# RFID_Brd_01.net
KiCad netlist of a schematic drawn in EAGLE
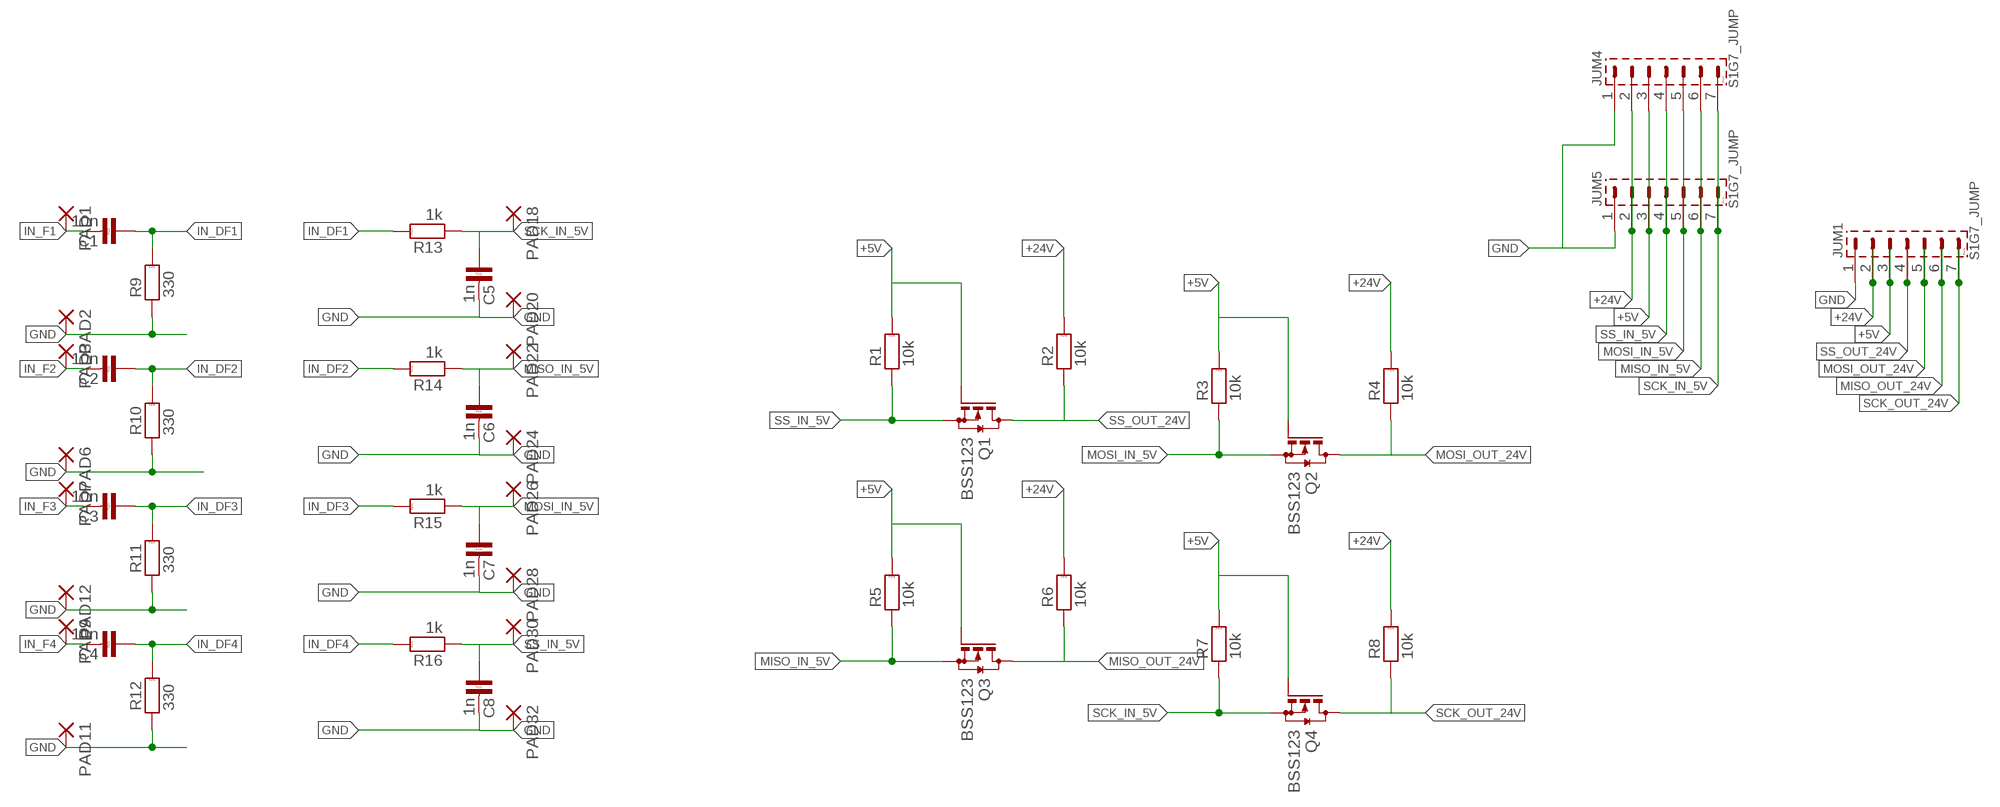
[diagram p0: schematic, sheet 1]

(export (version "E")
  (design (tool "Eeschema 10.0.6"))
  (components
    (comp (ref "C1")
      (value "10n")
      (footprint "eagle-import:1206")
      (libsource (lib "eagle-import") (part "C-KER_1206"))
    )
    (comp (ref "C2")
      (value "10n")
      (footprint "eagle-import:1206")
      (libsource (lib "eagle-import") (part "C-KER_1206"))
    )
    (comp (ref "C3")
      (value "10n")
      (footprint "eagle-import:1206")
      (libsource (lib "eagle-import") (part "C-KER_1206"))
    )
    (comp (ref "C4")
      (value "10n")
      (footprint "eagle-import:1206")
      (libsource (lib "eagle-import") (part "C-KER_1206"))
    )
    (comp (ref "C5")
      (value "1n")
      (footprint "eagle-import:1206")
      (libsource (lib "eagle-import") (part "C-KER_1206"))
    )
    (comp (ref "C6")
      (value "1n")
      (footprint "eagle-import:1206")
      (libsource (lib "eagle-import") (part "C-KER_1206"))
    )
    (comp (ref "C7")
      (value "1n")
      (footprint "eagle-import:1206")
      (libsource (lib "eagle-import") (part "C-KER_1206"))
    )
    (comp (ref "C8")
      (value "1n")
      (footprint "eagle-import:1206")
      (libsource (lib "eagle-import") (part "C-KER_1206"))
    )
    (comp (ref "JUM1")
      (value "S1G7_JUMP")
      (footprint "eagle-import:S1G7_JUM")
      (libsource (lib "eagle-import") (part "S1G7_JUMP"))
    )
    (comp (ref "JUM4")
      (value "S1G7_JUMP")
      (footprint "eagle-import:S1G7_JUM")
      (libsource (lib "eagle-import") (part "S1G7_JUMP"))
    )
    (comp (ref "JUM5")
      (value "S1G7_JUMP")
      (footprint "eagle-import:S1G7_JUM")
      (libsource (lib "eagle-import") (part "S1G7_JUMP"))
    )
    (comp (ref "PAD1")
      (value "SMD2")
      (footprint "eagle-import:SMD1,27-2,54")
      (libsource (lib "eagle-import") (part "SMD2"))
    )
    (comp (ref "PAD2")
      (value "SMD2")
      (footprint "eagle-import:SMD1,27-2,54")
      (libsource (lib "eagle-import") (part "SMD2"))
    )
    (comp (ref "PAD3")
      (value "SMD2")
      (footprint "eagle-import:SMD1,27-2,54")
      (libsource (lib "eagle-import") (part "SMD2"))
    )
    (comp (ref "PAD6")
      (value "SMD2")
      (footprint "eagle-import:SMD1,27-2,54")
      (libsource (lib "eagle-import") (part "SMD2"))
    )
    (comp (ref "PAD7")
      (value "SMD2")
      (footprint "eagle-import:SMD1,27-2,54")
      (libsource (lib "eagle-import") (part "SMD2"))
    )
    (comp (ref "PAD9")
      (value "SMD2")
      (footprint "eagle-import:SMD1,27-2,54")
      (libsource (lib "eagle-import") (part "SMD2"))
    )
    (comp (ref "PAD11")
      (value "SMD2")
      (footprint "eagle-import:SMD1,27-2,54")
      (libsource (lib "eagle-import") (part "SMD2"))
    )
    (comp (ref "PAD12")
      (value "SMD2")
      (footprint "eagle-import:SMD1,27-2,54")
      (libsource (lib "eagle-import") (part "SMD2"))
    )
    (comp (ref "PAD18")
      (value "SMD2")
      (footprint "eagle-import:SMD1,27-2,54")
      (libsource (lib "eagle-import") (part "SMD2"))
    )
    (comp (ref "PAD20")
      (value "SMD2")
      (footprint "eagle-import:SMD1,27-2,54")
      (libsource (lib "eagle-import") (part "SMD2"))
    )
    (comp (ref "PAD22")
      (value "SMD2")
      (footprint "eagle-import:SMD1,27-2,54")
      (libsource (lib "eagle-import") (part "SMD2"))
    )
    (comp (ref "PAD24")
      (value "SMD2")
      (footprint "eagle-import:SMD1,27-2,54")
      (libsource (lib "eagle-import") (part "SMD2"))
    )
    (comp (ref "PAD26")
      (value "SMD2")
      (footprint "eagle-import:SMD1,27-2,54")
      (libsource (lib "eagle-import") (part "SMD2"))
    )
    (comp (ref "PAD28")
      (value "SMD2")
      (footprint "eagle-import:SMD1,27-2,54")
      (libsource (lib "eagle-import") (part "SMD2"))
    )
    (comp (ref "PAD30")
      (value "SMD2")
      (footprint "eagle-import:SMD1,27-2,54")
      (libsource (lib "eagle-import") (part "SMD2"))
    )
    (comp (ref "PAD32")
      (value "SMD2")
      (footprint "eagle-import:SMD1,27-2,54")
      (libsource (lib "eagle-import") (part "SMD2"))
    )
    (comp (ref "Q1")
      (value "BSS123")
      (footprint "eagle-import:SOT23")
      (libsource (lib "eagle-import") (part "BSS123"))
    )
    (comp (ref "Q2")
      (value "BSS123")
      (footprint "eagle-import:SOT23")
      (libsource (lib "eagle-import") (part "BSS123"))
    )
    (comp (ref "Q3")
      (value "BSS123")
      (footprint "eagle-import:SOT23")
      (libsource (lib "eagle-import") (part "BSS123"))
    )
    (comp (ref "Q4")
      (value "BSS123")
      (footprint "eagle-import:SOT23")
      (libsource (lib "eagle-import") (part "BSS123"))
    )
    (comp (ref "R1")
      (value "10k")
      (footprint "eagle-import:1206")
      (libsource (lib "eagle-import") (part "R_1206"))
    )
    (comp (ref "R2")
      (value "10k")
      (footprint "eagle-import:1206")
      (libsource (lib "eagle-import") (part "R_1206"))
    )
    (comp (ref "R3")
      (value "10k")
      (footprint "eagle-import:1206")
      (libsource (lib "eagle-import") (part "R_1206"))
    )
    (comp (ref "R4")
      (value "10k")
      (footprint "eagle-import:1206")
      (libsource (lib "eagle-import") (part "R_1206"))
    )
    (comp (ref "R5")
      (value "10k")
      (footprint "eagle-import:1206")
      (libsource (lib "eagle-import") (part "R_1206"))
    )
    (comp (ref "R6")
      (value "10k")
      (footprint "eagle-import:1206")
      (libsource (lib "eagle-import") (part "R_1206"))
    )
    (comp (ref "R7")
      (value "10k")
      (footprint "eagle-import:1206")
      (libsource (lib "eagle-import") (part "R_1206"))
    )
    (comp (ref "R8")
      (value "10k")
      (footprint "eagle-import:1206")
      (libsource (lib "eagle-import") (part "R_1206"))
    )
    (comp (ref "R9")
      (value "330")
      (footprint "eagle-import:1206")
      (libsource (lib "eagle-import") (part "R_1206"))
    )
    (comp (ref "R10")
      (value "330")
      (footprint "eagle-import:1206")
      (libsource (lib "eagle-import") (part "R_1206"))
    )
    (comp (ref "R11")
      (value "330")
      (footprint "eagle-import:1206")
      (libsource (lib "eagle-import") (part "R_1206"))
    )
    (comp (ref "R12")
      (value "330")
      (footprint "eagle-import:1206")
      (libsource (lib "eagle-import") (part "R_1206"))
    )
    (comp (ref "R13")
      (value "1k")
      (footprint "eagle-import:1206")
      (libsource (lib "eagle-import") (part "R_1206"))
    )
    (comp (ref "R14")
      (value "1k")
      (footprint "eagle-import:1206")
      (libsource (lib "eagle-import") (part "R_1206"))
    )
    (comp (ref "R15")
      (value "1k")
      (footprint "eagle-import:1206")
      (libsource (lib "eagle-import") (part "R_1206"))
    )
    (comp (ref "R16")
      (value "1k")
      (footprint "eagle-import:1206")
      (libsource (lib "eagle-import") (part "R_1206"))
    )
  )
  (nets
    (net (code "1") (name "+5V") (class "Default")
      (node (ref "JUM1") (pin "3") (pinfunction "3_3") (pintype "passive"))
      (node (ref "JUM4") (pin "3") (pinfunction "3_3") (pintype "passive"))
      (node (ref "JUM5") (pin "3") (pinfunction "3_3") (pintype "passive"))
      (node (ref "Q1") (pin "1") (pinfunction "G_1") (pintype "passive"))
      (node (ref "Q2") (pin "1") (pinfunction "G_1") (pintype "passive"))
      (node (ref "Q3") (pin "1") (pinfunction "G_1") (pintype "passive"))
      (node (ref "Q4") (pin "1") (pinfunction "G_1") (pintype "passive"))
      (node (ref "R1") (pin "2") (pinfunction "2_2") (pintype "passive"))
      (node (ref "R3") (pin "2") (pinfunction "2_2") (pintype "passive"))
      (node (ref "R5") (pin "2") (pinfunction "2_2") (pintype "passive"))
      (node (ref "R7") (pin "2") (pinfunction "2_2") (pintype "passive"))
    )
    (net (code "2") (name "+24V") (class "Default")
      (node (ref "JUM1") (pin "2") (pinfunction "2_2") (pintype "passive"))
      (node (ref "JUM4") (pin "2") (pinfunction "2_2") (pintype "passive"))
      (node (ref "JUM5") (pin "2") (pinfunction "2_2") (pintype "passive"))
      (node (ref "R2") (pin "2") (pinfunction "2_2") (pintype "passive"))
      (node (ref "R4") (pin "2") (pinfunction "2_2") (pintype "passive"))
      (node (ref "R6") (pin "2") (pinfunction "2_2") (pintype "passive"))
      (node (ref "R8") (pin "2") (pinfunction "2_2") (pintype "passive"))
    )
    (net (code "3") (name "GND") (class "Default")
      (node (ref "C5") (pin "2") (pinfunction "2_2") (pintype "passive"))
      (node (ref "C6") (pin "2") (pinfunction "2_2") (pintype "passive"))
      (node (ref "C7") (pin "2") (pinfunction "2_2") (pintype "passive"))
      (node (ref "C8") (pin "2") (pinfunction "2_2") (pintype "passive"))
      (node (ref "JUM1") (pin "1") (pinfunction "1_1") (pintype "passive"))
      (node (ref "JUM4") (pin "1") (pinfunction "1_1") (pintype "passive"))
      (node (ref "JUM5") (pin "1") (pinfunction "1_1") (pintype "passive"))
      (node (ref "PAD11") (pin "1") (pinfunction "P_1") (pintype "passive"))
      (node (ref "PAD12") (pin "1") (pinfunction "P_1") (pintype "passive"))
      (node (ref "PAD2") (pin "1") (pinfunction "P_1") (pintype "passive"))
      (node (ref "PAD20") (pin "1") (pinfunction "P_1") (pintype "passive"))
      (node (ref "PAD24") (pin "1") (pinfunction "P_1") (pintype "passive"))
      (node (ref "PAD28") (pin "1") (pinfunction "P_1") (pintype "passive"))
      (node (ref "PAD32") (pin "1") (pinfunction "P_1") (pintype "passive"))
      (node (ref "PAD6") (pin "1") (pinfunction "P_1") (pintype "passive"))
      (node (ref "R10") (pin "1") (pinfunction "1_1") (pintype "passive"))
      (node (ref "R11") (pin "1") (pinfunction "1_1") (pintype "passive"))
      (node (ref "R12") (pin "1") (pinfunction "1_1") (pintype "passive"))
      (node (ref "R9") (pin "1") (pinfunction "1_1") (pintype "passive"))
    )
    (net (code "4") (name "IN_DF1") (class "Default")
      (node (ref "C1") (pin "1") (pinfunction "1_1") (pintype "passive"))
      (node (ref "R13") (pin "2") (pinfunction "2_2") (pintype "passive"))
      (node (ref "R9") (pin "2") (pinfunction "2_2") (pintype "passive"))
    )
    (net (code "5") (name "IN_DF2") (class "Default")
      (node (ref "C2") (pin "1") (pinfunction "1_1") (pintype "passive"))
      (node (ref "R10") (pin "2") (pinfunction "2_2") (pintype "passive"))
      (node (ref "R14") (pin "2") (pinfunction "2_2") (pintype "passive"))
    )
    (net (code "6") (name "IN_DF3") (class "Default")
      (node (ref "C3") (pin "1") (pinfunction "1_1") (pintype "passive"))
      (node (ref "R11") (pin "2") (pinfunction "2_2") (pintype "passive"))
      (node (ref "R15") (pin "2") (pinfunction "2_2") (pintype "passive"))
    )
    (net (code "7") (name "IN_DF4") (class "Default")
      (node (ref "C4") (pin "1") (pinfunction "1_1") (pintype "passive"))
      (node (ref "R12") (pin "2") (pinfunction "2_2") (pintype "passive"))
      (node (ref "R16") (pin "2") (pinfunction "2_2") (pintype "passive"))
    )
    (net (code "8") (name "IN_F1") (class "Default")
      (node (ref "C1") (pin "2") (pinfunction "2_2") (pintype "passive"))
      (node (ref "PAD1") (pin "1") (pinfunction "P_1") (pintype "passive"))
    )
    (net (code "9") (name "IN_F2") (class "Default")
      (node (ref "C2") (pin "2") (pinfunction "2_2") (pintype "passive"))
      (node (ref "PAD3") (pin "1") (pinfunction "P_1") (pintype "passive"))
    )
    (net (code "10") (name "IN_F3") (class "Default")
      (node (ref "C3") (pin "2") (pinfunction "2_2") (pintype "passive"))
      (node (ref "PAD7") (pin "1") (pinfunction "P_1") (pintype "passive"))
    )
    (net (code "11") (name "IN_F4") (class "Default")
      (node (ref "C4") (pin "2") (pinfunction "2_2") (pintype "passive"))
      (node (ref "PAD9") (pin "1") (pinfunction "P_1") (pintype "passive"))
    )
    (net (code "12") (name "MISO_IN_5V") (class "Default")
      (node (ref "C6") (pin "1") (pinfunction "1_1") (pintype "passive"))
      (node (ref "JUM4") (pin "6") (pinfunction "6_6") (pintype "passive"))
      (node (ref "JUM5") (pin "6") (pinfunction "6_6") (pintype "passive"))
      (node (ref "PAD22") (pin "1") (pinfunction "P_1") (pintype "passive"))
      (node (ref "Q3") (pin "2") (pinfunction "S_2") (pintype "passive"))
      (node (ref "R14") (pin "1") (pinfunction "1_1") (pintype "passive"))
      (node (ref "R5") (pin "1") (pinfunction "1_1") (pintype "passive"))
    )
    (net (code "13") (name "MISO_OUT_24V") (class "Default")
      (node (ref "JUM1") (pin "6") (pinfunction "6_6") (pintype "passive"))
      (node (ref "Q3") (pin "3") (pinfunction "D_3") (pintype "passive"))
      (node (ref "R6") (pin "1") (pinfunction "1_1") (pintype "passive"))
    )
    (net (code "14") (name "MOSI_IN_5V") (class "Default")
      (node (ref "C7") (pin "1") (pinfunction "1_1") (pintype "passive"))
      (node (ref "JUM4") (pin "5") (pinfunction "5_5") (pintype "passive"))
      (node (ref "JUM5") (pin "5") (pinfunction "5_5") (pintype "passive"))
      (node (ref "PAD26") (pin "1") (pinfunction "P_1") (pintype "passive"))
      (node (ref "Q2") (pin "2") (pinfunction "S_2") (pintype "passive"))
      (node (ref "R15") (pin "1") (pinfunction "1_1") (pintype "passive"))
      (node (ref "R3") (pin "1") (pinfunction "1_1") (pintype "passive"))
    )
    (net (code "15") (name "MOSI_OUT_24V") (class "Default")
      (node (ref "JUM1") (pin "5") (pinfunction "5_5") (pintype "passive"))
      (node (ref "Q2") (pin "3") (pinfunction "D_3") (pintype "passive"))
      (node (ref "R4") (pin "1") (pinfunction "1_1") (pintype "passive"))
    )
    (net (code "16") (name "SCK_IN_5V") (class "Default")
      (node (ref "C5") (pin "1") (pinfunction "1_1") (pintype "passive"))
      (node (ref "JUM4") (pin "7") (pinfunction "7_7") (pintype "passive"))
      (node (ref "JUM5") (pin "7") (pinfunction "7_7") (pintype "passive"))
      (node (ref "PAD18") (pin "1") (pinfunction "P_1") (pintype "passive"))
      (node (ref "Q4") (pin "2") (pinfunction "S_2") (pintype "passive"))
      (node (ref "R13") (pin "1") (pinfunction "1_1") (pintype "passive"))
      (node (ref "R7") (pin "1") (pinfunction "1_1") (pintype "passive"))
    )
    (net (code "17") (name "SCK_OUT_24V") (class "Default")
      (node (ref "JUM1") (pin "7") (pinfunction "7_7") (pintype "passive"))
      (node (ref "Q4") (pin "3") (pinfunction "D_3") (pintype "passive"))
      (node (ref "R8") (pin "1") (pinfunction "1_1") (pintype "passive"))
    )
    (net (code "18") (name "SS_IN_5V") (class "Default")
      (node (ref "C8") (pin "1") (pinfunction "1_1") (pintype "passive"))
      (node (ref "JUM4") (pin "4") (pinfunction "4_4") (pintype "passive"))
      (node (ref "JUM5") (pin "4") (pinfunction "4_4") (pintype "passive"))
      (node (ref "PAD30") (pin "1") (pinfunction "P_1") (pintype "passive"))
      (node (ref "Q1") (pin "2") (pinfunction "S_2") (pintype "passive"))
      (node (ref "R1") (pin "1") (pinfunction "1_1") (pintype "passive"))
      (node (ref "R16") (pin "1") (pinfunction "1_1") (pintype "passive"))
    )
    (net (code "19") (name "SS_OUT_24V") (class "Default")
      (node (ref "JUM1") (pin "4") (pinfunction "4_4") (pintype "passive"))
      (node (ref "Q1") (pin "3") (pinfunction "D_3") (pintype "passive"))
      (node (ref "R2") (pin "1") (pinfunction "1_1") (pintype "passive"))
    )
  )
)
